# Adafruit_MatrixPortal_S3.net
KiCad netlist of a schematic drawn in EAGLE
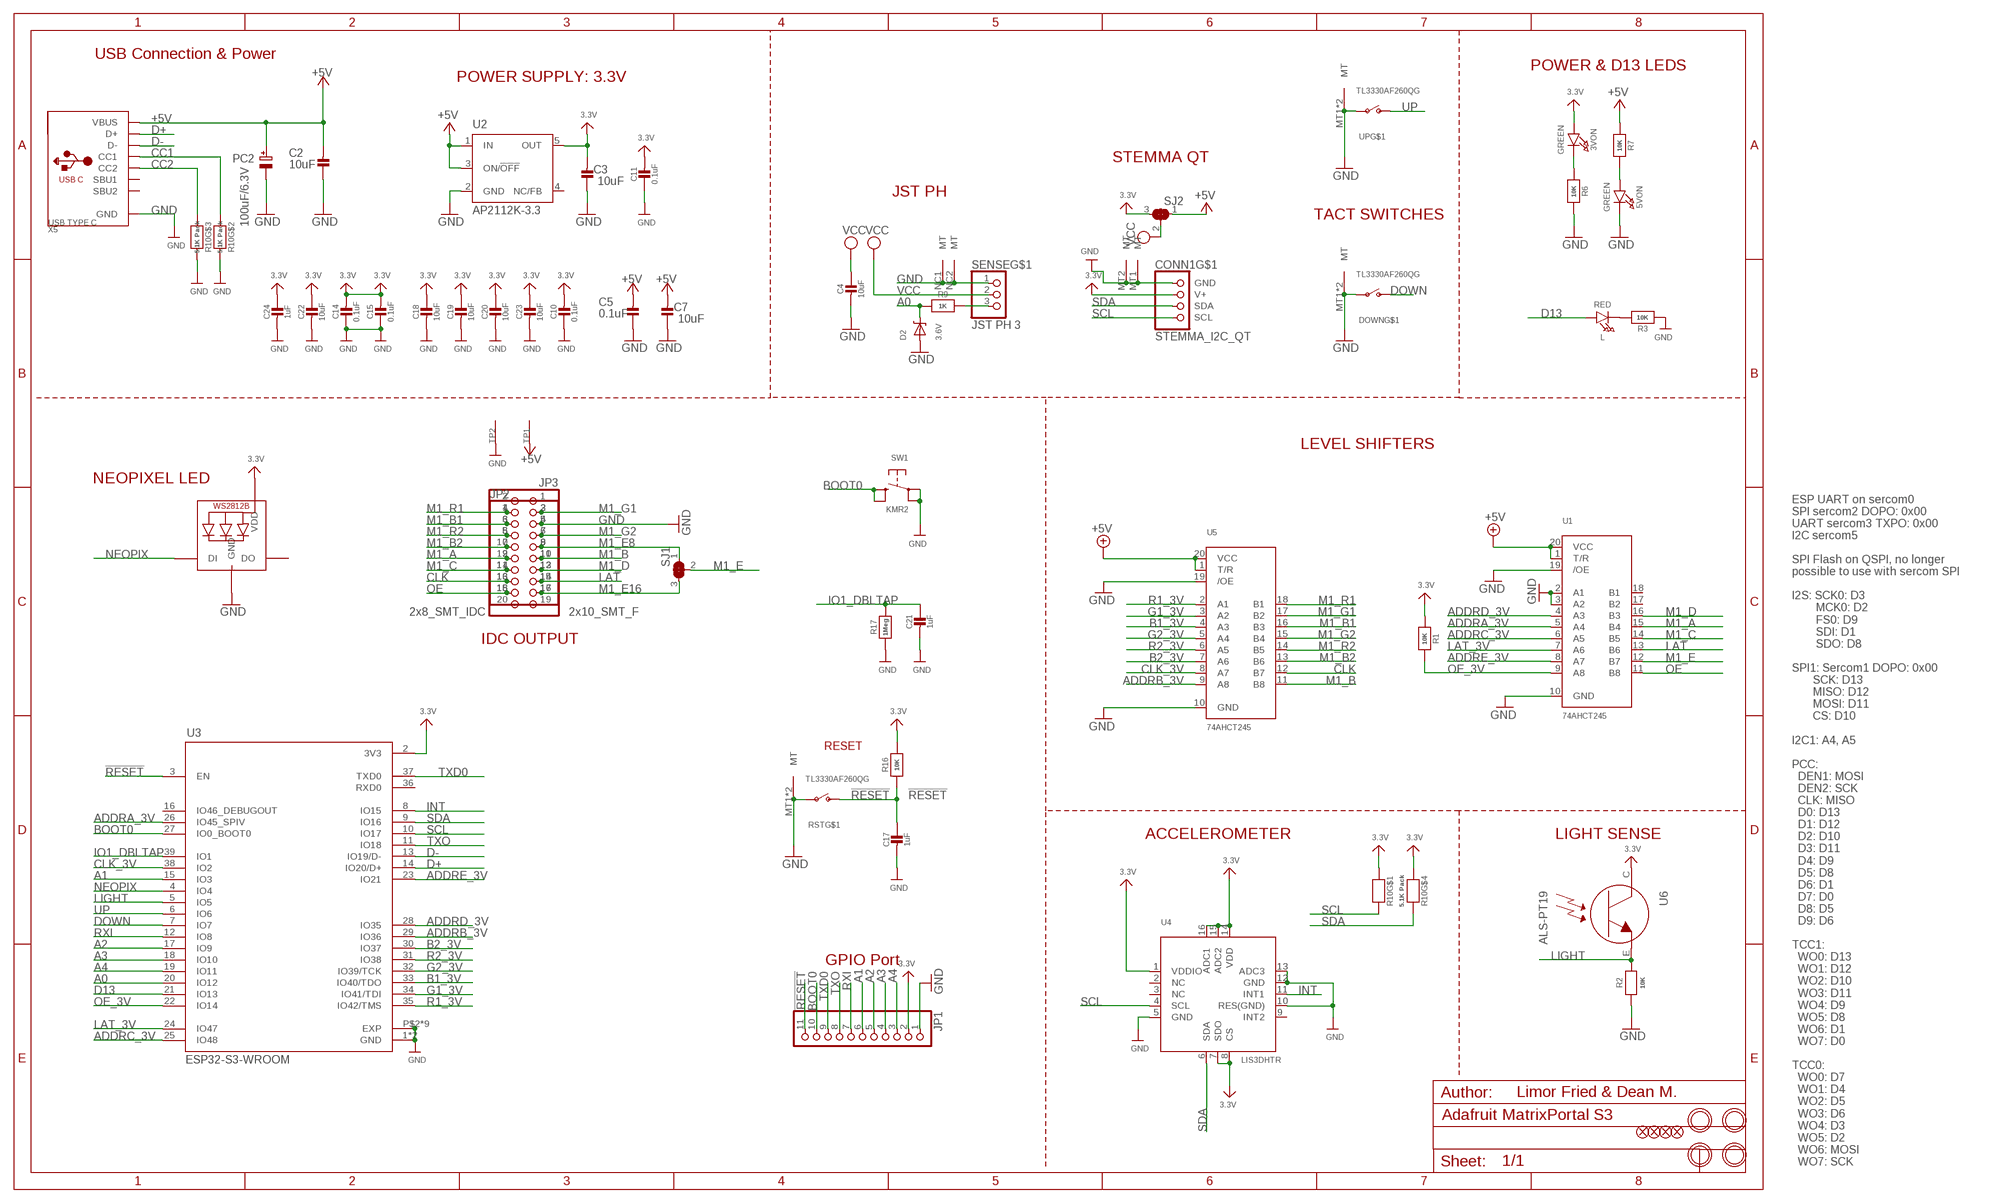
[diagram p0: schematic, sheet 1]

(export (version "E")
  (design (tool "Eeschema 10.0.6"))
  (components
    (comp (ref "3VON")
      (value "GREEN")
      (footprint "eagle-import:CHIPLED_0603_NOOUTLINE")
      (libsource (lib "eagle-import") (part "LED0603_NOOUTLINE"))
    )
    (comp (ref "5VON")
      (value "GREEN")
      (footprint "eagle-import:CHIPLED_0603_NOOUTLINE")
      (libsource (lib "eagle-import") (part "LED0603_NOOUTLINE"))
    )
    (comp (ref "C2")
      (value "10uF")
      (footprint "eagle-import:0805-NO")
      (libsource (lib "eagle-import") (part "CAP_CERAMIC0805-NOOUTLINE"))
    )
    (comp (ref "C3")
      (value "10uF")
      (footprint "eagle-import:0805-NO")
      (libsource (lib "eagle-import") (part "CAP_CERAMIC0805-NOOUTLINE"))
    )
    (comp (ref "C4")
      (value "10uF")
      (footprint "eagle-import:0805-NO")
      (libsource (lib "eagle-import") (part "CAP_CERAMIC0805-NOOUTLINE"))
    )
    (comp (ref "C5")
      (value "0.1uF")
      (footprint "eagle-import:0603-NO")
      (libsource (lib "eagle-import") (part "CAP_CERAMIC0603_NO"))
    )
    (comp (ref "C7")
      (value "10uF")
      (footprint "eagle-import:0805-NO")
      (libsource (lib "eagle-import") (part "CAP_CERAMIC0805-NOOUTLINE"))
    )
    (comp (ref "C10")
      (value "0.1uF")
      (footprint "eagle-import:0603-NO")
      (libsource (lib "eagle-import") (part "CAP_CERAMIC0603_NO"))
    )
    (comp (ref "C11")
      (value "0.1uF")
      (footprint "eagle-import:0603-NO")
      (libsource (lib "eagle-import") (part "CAP_CERAMIC0603_NO"))
    )
    (comp (ref "C14")
      (value "0.1uF")
      (footprint "eagle-import:0603-NO")
      (libsource (lib "eagle-import") (part "CAP_CERAMIC0603_NO"))
    )
    (comp (ref "C15")
      (value "0.1uF")
      (footprint "eagle-import:0603-NO")
      (libsource (lib "eagle-import") (part "CAP_CERAMIC0603_NO"))
    )
    (comp (ref "C17")
      (value "1uF")
      (footprint "eagle-import:0603-NO")
      (libsource (lib "eagle-import") (part "CAP_CERAMIC0603_NO"))
    )
    (comp (ref "C18")
      (value "10uF")
      (footprint "eagle-import:0805-NO")
      (libsource (lib "eagle-import") (part "CAP_CERAMIC0805-NOOUTLINE"))
    )
    (comp (ref "C19")
      (value "10uF")
      (footprint "eagle-import:0805-NO")
      (libsource (lib "eagle-import") (part "CAP_CERAMIC0805-NOOUTLINE"))
    )
    (comp (ref "C20")
      (value "10uF")
      (footprint "eagle-import:0805-NO")
      (libsource (lib "eagle-import") (part "CAP_CERAMIC0805-NOOUTLINE"))
    )
    (comp (ref "C21")
      (value "1uF")
      (footprint "eagle-import:0603-NO")
      (libsource (lib "eagle-import") (part "CAP_CERAMIC0603_NO"))
    )
    (comp (ref "C22")
      (value "10uF")
      (footprint "eagle-import:0805-NO")
      (libsource (lib "eagle-import") (part "CAP_CERAMIC0805-NOOUTLINE"))
    )
    (comp (ref "C23")
      (value "10uF")
      (footprint "eagle-import:0805-NO")
      (libsource (lib "eagle-import") (part "CAP_CERAMIC0805-NOOUTLINE"))
    )
    (comp (ref "C24")
      (value "1uF")
      (footprint "eagle-import:0603-NO")
      (libsource (lib "eagle-import") (part "CAP_CERAMIC0603_NO"))
    )
    (comp (ref "CONN1")
      (value "STEMMA_I2C_QT")
      (footprint "eagle-import:JST_SH4")
      (libsource (lib "eagle-import") (part "STEMMA_I2C_QT"))
    )
    (comp (ref "D2")
      (value "3.6V")
      (footprint "eagle-import:SOD-323")
      (libsource (lib "eagle-import") (part "DIODE-ZENERSOD323"))
    )
    (comp (ref "DOWN")
      (value "TL3330AF260QG")
      (footprint "eagle-import:SPST_TACTILE_RA")
      (libsource (lib "eagle-import") (part "SWITCH_SPST_MNT_TACT_RA"))
    )
    (comp (ref "FID1")
      (value "FIDUCIAL_1MM")
      (footprint "eagle-import:FIDUCIAL_1MM")
      (libsource (lib "eagle-import") (part "FIDUCIAL_1MM"))
    )
    (comp (ref "FID2")
      (value "FIDUCIAL_1MM")
      (footprint "eagle-import:FIDUCIAL_1MM")
      (libsource (lib "eagle-import") (part "FIDUCIAL_1MM"))
    )
    (comp (ref "FID3")
      (value "FIDUCIAL_1MM")
      (footprint "eagle-import:FIDUCIAL_1MM")
      (libsource (lib "eagle-import") (part "FIDUCIAL_1MM"))
    )
    (comp (ref "FID4")
      (value "FIDUCIAL_1MM")
      (footprint "eagle-import:FIDUCIAL_1MM")
      (libsource (lib "eagle-import") (part "FIDUCIAL_1MM"))
    )
    (comp (ref "JP1")
      (value "HEADER-1X11")
      (footprint "eagle-import:1X11_ROUND")
      (libsource (lib "eagle-import") (part "HEADER-1X11"))
    )
    (comp (ref "JP2")
      (value "2x8_SMT_IDC")
      (footprint "eagle-import:2X08_SHROUDEDSMT")
      (libsource (lib "eagle-import") (part "HEADER-2X8_SHROUDEDSMT"))
    )
    (comp (ref "JP3")
      (value "2x10_SMT_F")
      (footprint "eagle-import:2X10_SMT_FEMALE")
      (libsource (lib "eagle-import") (part "HEADER-2X10SMT_FEMALE"))
    )
    (comp (ref "L")
      (value "RED")
      (footprint "eagle-import:CHIPLED_0603_NOOUTLINE")
      (libsource (lib "eagle-import") (part "LED0603_NOOUTLINE"))
    )
    (comp (ref "LED1")
      (value "WS2812B_3535FULL")
      (footprint "eagle-import:LED3535_FULLPADS")
      (libsource (lib "eagle-import") (part "WS2812B_3535FULL"))
    )
    (comp (ref "PC2")
      (value "100uF/6.3V")
      (footprint "eagle-import:PANASONIC_D")
      (libsource (lib "eagle-import") (part "CAP_ELECTROLYTICPANASONIC_D"))
    )
    (comp (ref "R1")
      (value "10K")
      (footprint "eagle-import:0603-NO")
      (libsource (lib "eagle-import") (part "RESISTOR_0603_NOOUT"))
    )
    (comp (ref "R2")
      (value "10K")
      (footprint "eagle-import:0603-NO")
      (libsource (lib "eagle-import") (part "RESISTOR_0603_NOOUT"))
    )
    (comp (ref "R3")
      (value "10K")
      (footprint "eagle-import:0603-NO")
      (libsource (lib "eagle-import") (part "RESISTOR_0603_NOOUT"))
    )
    (comp (ref "R6")
      (value "10K")
      (footprint "eagle-import:0603-NO")
      (libsource (lib "eagle-import") (part "RESISTOR_0603_NOOUT"))
    )
    (comp (ref "R7")
      (value "10K")
      (footprint "eagle-import:0603-NO")
      (libsource (lib "eagle-import") (part "RESISTOR_0603_NOOUT"))
    )
    (comp (ref "R9")
      (value "1K")
      (footprint "eagle-import:0603-NO")
      (libsource (lib "eagle-import") (part "RESISTOR_0603_NOOUT"))
    )
    (comp (ref "R10")
      (value "5.1K Pack")
      (footprint "eagle-import:RESPACK_4X0603")
      (libsource (lib "eagle-import") (part "RESISTOR_4PACK"))
    )
    (comp (ref "R16")
      (value "10K")
      (footprint "eagle-import:0603-NO")
      (libsource (lib "eagle-import") (part "RESISTOR_0603_NOOUT"))
    )
    (comp (ref "R17")
      (value "1Meg")
      (footprint "eagle-import:0603-NO")
      (libsource (lib "eagle-import") (part "RESISTOR_0603_NOOUT"))
    )
    (comp (ref "RST")
      (value "TL3330AF260QG")
      (footprint "eagle-import:SPST_TACTILE_RA")
      (libsource (lib "eagle-import") (part "SWITCH_SPST_MNT_TACT_RA"))
    )
    (comp (ref "SENSE")
      (value "JST PH 3")
      (footprint "eagle-import:JSTPH3")
      (libsource (lib "eagle-import") (part "CON_JST_PH_3PIN"))
    )
    (comp (ref "SJ1")
      (value "SOLDERJUMPER_2WAY")
      (footprint "eagle-import:SOLDERJUMPER_2WAY_OPEN_NOPASTE")
      (libsource (lib "eagle-import") (part "SOLDERJUMPER_2WAY"))
    )
    (comp (ref "SJ2")
      (value "SOLDERJUMPER_2WAY")
      (footprint "eagle-import:SOLDERJUMPER_2WAY_OPEN_NOPASTE")
      (libsource (lib "eagle-import") (part "SOLDERJUMPER_2WAY"))
    )
    (comp (ref "SW1")
      (value "KMR2")
      (footprint "eagle-import:BTN_RKB2_4.6X2.8")
      (libsource (lib "eagle-import") (part "SWITCH_TACT_SMT_RKB2"))
    )
    (comp (ref "TP1")
      (value "SEWTAP_SMTNUTM3")
      (footprint "eagle-import:SMT_NUT_3MM")
      (libsource (lib "eagle-import") (part "SEWTAP_SMTNUTM3"))
    )
    (comp (ref "TP2")
      (value "SEWTAP_SMTNUTM3")
      (footprint "eagle-import:SMT_NUT_3MM")
      (libsource (lib "eagle-import") (part "SEWTAP_SMTNUTM3"))
    )
    (comp (ref "U$14")
      (value "MOUNTINGHOLE2.5")
      (footprint "eagle-import:MOUNTINGHOLE_2.5_PLATED")
      (libsource (lib "eagle-import") (part "MOUNTINGHOLE2.5"))
    )
    (comp (ref "U$19")
      (value "MOUNTINGHOLE2.5")
      (footprint "eagle-import:MOUNTINGHOLE_2.5_PLATED")
      (libsource (lib "eagle-import") (part "MOUNTINGHOLE2.5"))
    )
    (comp (ref "U$22")
      (value "MOUNTINGHOLE2.5")
      (footprint "eagle-import:MOUNTINGHOLE_2.5_PLATED")
      (libsource (lib "eagle-import") (part "MOUNTINGHOLE2.5"))
    )
    (comp (ref "U$24")
      (value "MOUNTINGHOLE2.5")
      (footprint "eagle-import:MOUNTINGHOLE_2.5_PLATED")
      (libsource (lib "eagle-import") (part "MOUNTINGHOLE2.5"))
    )
    (comp (ref "U1")
      (value "74AHCT245")
      (footprint "eagle-import:TSSOP20")
      (libsource (lib "eagle-import") (part "74LCX245_TSSOP20"))
    )
    (comp (ref "U2")
      (value "AP2112K-3.3")
      (footprint "eagle-import:SOT23-DBV")
      (libsource (lib "eagle-import") (part "LP2985-XXDBVR33"))
    )
    (comp (ref "U3")
      (value "ESP32-S3-WROOM")
      (footprint "eagle-import:S3-WROOM32")
      (libsource (lib "eagle-import") (part "ESP32-S3-WROOM"))
    )
    (comp (ref "U4")
      (value "LIS3DHTR")
      (footprint "eagle-import:LGA16_3X3MM")
      (libsource (lib "eagle-import") (part "ACCEL_LIS3DHTR"))
    )
    (comp (ref "U5")
      (value "74AHCT245")
      (footprint "eagle-import:TSSOP20")
      (libsource (lib "eagle-import") (part "74LCX245_TSSOP20"))
    )
    (comp (ref "U6")
      (value "ALS-PT19")
      (footprint "eagle-import:ALS-PT19-315C")
      (libsource (lib "eagle-import") (part "PHOTOTRANSISTOR_PT19-315C"))
    )
    (comp (ref "UP")
      (value "TL3330AF260QG")
      (footprint "eagle-import:SPST_TACTILE_RA")
      (libsource (lib "eagle-import") (part "SWITCH_SPST_MNT_TACT_RA"))
    )
    (comp (ref "X5")
      (value "USB TYPE C")
      (footprint "eagle-import:USB_C_CUSB31-CFM2AX-01-X")
      (libsource (lib "eagle-import") (part "USB_C"))
    )
  )
  (nets
    (net (code "1") (name "+5V") (class "Default")
      (node (ref "C2") (pin "2") (pinfunction "2_2") (pintype "passive"))
      (node (ref "C5") (pin "2") (pinfunction "2_2") (pintype "passive"))
      (node (ref "C7") (pin "2") (pinfunction "2_2") (pintype "passive"))
      (node (ref "PC2") (pin "+") (pinfunction "+_+") (pintype "passive"))
      (node (ref "R7") (pin "1") (pinfunction "1_1") (pintype "passive"))
      (node (ref "SJ2") (pin "1") (pinfunction "1_1") (pintype "passive"))
      (node (ref "TP1") (pin "P$1") (pinfunction "SEW_P$1") (pintype "bidirectional"))
      (node (ref "U1") (pin "1") (pinfunction "T/R_1") (pintype "bidirectional"))
      (node (ref "U1") (pin "20") (pinfunction "VCC_20") (pintype "bidirectional"))
      (node (ref "U2") (pin "1") (pinfunction "IN_1") (pintype "input"))
      (node (ref "U2") (pin "3") (pinfunction "ON/~{OFF}_3") (pintype "input"))
      (node (ref "U5") (pin "1") (pinfunction "T/R_1") (pintype "bidirectional"))
      (node (ref "U5") (pin "20") (pinfunction "VCC_20") (pintype "bidirectional"))
      (node (ref "X5") (pin "A4B9") (pinfunction "VBUS_A4B9") (pintype "power_in"))
      (node (ref "X5") (pin "B4A9") (pinfunction "VBUS_B4A9") (pintype "power_in"))
    )
    (net (code "2") (name "/A0") (class "Default")
      (node (ref "D2") (pin "C") (pinfunction "C_C") (pintype "passive"))
      (node (ref "R9") (pin "2") (pinfunction "2_2") (pintype "passive"))
      (node (ref "U3") (pin "20") (pinfunction "IO12_20") (pintype "bidirectional"))
    )
    (net (code "3") (name "/A1") (class "Default")
      (node (ref "JP1") (pin "6") (pinfunction "6_6") (pintype "passive"))
      (node (ref "U3") (pin "15") (pinfunction "IO3_15") (pintype "bidirectional"))
    )
    (net (code "4") (name "/A2") (class "Default")
      (node (ref "JP1") (pin "5") (pinfunction "5_5") (pintype "passive"))
      (node (ref "U3") (pin "17") (pinfunction "IO9_17") (pintype "bidirectional"))
    )
    (net (code "5") (name "/A3") (class "Default")
      (node (ref "JP1") (pin "4") (pinfunction "4_4") (pintype "passive"))
      (node (ref "U3") (pin "18") (pinfunction "IO10_18") (pintype "bidirectional"))
    )
    (net (code "6") (name "/A4") (class "Default")
      (node (ref "JP1") (pin "3") (pinfunction "3_3") (pintype "passive"))
      (node (ref "U3") (pin "19") (pinfunction "IO11_19") (pintype "bidirectional"))
    )
    (net (code "7") (name "/ADDRA_3V") (class "Default")
      (node (ref "U1") (pin "5") (pinfunction "A4_5") (pintype "bidirectional"))
      (node (ref "U3") (pin "26") (pinfunction "IO45_SPIV_26") (pintype "bidirectional"))
    )
    (net (code "8") (name "/ADDRB_3V") (class "Default")
      (node (ref "U3") (pin "29") (pinfunction "IO36_29") (pintype "bidirectional"))
      (node (ref "U5") (pin "9") (pinfunction "A8_9") (pintype "bidirectional"))
    )
    (net (code "9") (name "/ADDRC_3V") (class "Default")
      (node (ref "U1") (pin "6") (pinfunction "A5_6") (pintype "bidirectional"))
      (node (ref "U3") (pin "25") (pinfunction "IO48_25") (pintype "input"))
    )
    (net (code "10") (name "/ADDRD_3V") (class "Default")
      (node (ref "U1") (pin "4") (pinfunction "A3_4") (pintype "bidirectional"))
      (node (ref "U3") (pin "28") (pinfunction "IO35_28") (pintype "input"))
    )
    (net (code "11") (name "/ADDRE_3V") (class "Default")
      (node (ref "U1") (pin "8") (pinfunction "A7_8") (pintype "bidirectional"))
      (node (ref "U3") (pin "23") (pinfunction "IO21_23") (pintype "bidirectional"))
    )
    (net (code "12") (name "/B1_3V") (class "Default")
      (node (ref "U3") (pin "33") (pinfunction "IO40/TDO_33") (pintype "bidirectional"))
      (node (ref "U5") (pin "4") (pinfunction "A3_4") (pintype "bidirectional"))
    )
    (net (code "13") (name "/B2_3V") (class "Default")
      (node (ref "U3") (pin "30") (pinfunction "IO37_30") (pintype "bidirectional"))
      (node (ref "U5") (pin "7") (pinfunction "A6_7") (pintype "bidirectional"))
    )
    (net (code "14") (name "/BOOT0") (class "Default")
      (node (ref "JP1") (pin "10") (pinfunction "10_10") (pintype "passive"))
      (node (ref "SW1") (pin "B") (pinfunction "S_B") (pintype "passive"))
      (node (ref "SW1") (pin "B'") (pinfunction "S1_B'") (pintype "passive"))
      (node (ref "U3") (pin "27") (pinfunction "IO0_BOOT0_27") (pintype "bidirectional"))
    )
    (net (code "15") (name "/CC1") (class "Default")
      (node (ref "R10") (pin "2") (pinfunction "1_2") (pintype "passive"))
      (node (ref "X5") (pin "A5") (pinfunction "CC1_A5") (pintype "bidirectional"))
    )
    (net (code "16") (name "/CC2") (class "Default")
      (node (ref "R10") (pin "3") (pinfunction "1_3") (pintype "passive"))
      (node (ref "X5") (pin "B5") (pinfunction "CC2_B5") (pintype "bidirectional"))
    )
    (net (code "17") (name "/CLK") (class "Default")
      (node (ref "JP2") (pin "13") (pinfunction "13_13") (pintype "passive"))
      (node (ref "JP3") (pin "16") (pinfunction "16_16") (pintype "passive"))
      (node (ref "U5") (pin "12") (pinfunction "B7_12") (pintype "bidirectional"))
    )
    (net (code "18") (name "/CLK_3V") (class "Default")
      (node (ref "U3") (pin "38") (pinfunction "IO2_38") (pintype "bidirectional"))
      (node (ref "U5") (pin "8") (pinfunction "A7_8") (pintype "bidirectional"))
    )
    (net (code "19") (name "/D+") (class "Default")
      (node (ref "U3") (pin "14") (pinfunction "IO20/D+_14") (pintype "bidirectional"))
      (node (ref "X5") (pin "A6") (pinfunction "D+_A6") (pintype "bidirectional"))
      (node (ref "X5") (pin "B6") (pinfunction "D+_B6") (pintype "bidirectional"))
    )
    (net (code "20") (name "/D-") (class "Default")
      (node (ref "U3") (pin "13") (pinfunction "IO19/D-_13") (pintype "bidirectional"))
      (node (ref "X5") (pin "A7") (pinfunction "D-_A7") (pintype "bidirectional"))
      (node (ref "X5") (pin "B7") (pinfunction "D-_B7") (pintype "bidirectional"))
    )
    (net (code "21") (name "/D13") (class "Default")
      (node (ref "L") (pin "A") (pinfunction "A_A") (pintype "passive"))
      (node (ref "U3") (pin "21") (pinfunction "IO13_21") (pintype "bidirectional"))
    )
    (net (code "22") (name "/DOWN") (class "Default")
      (node (ref "DOWN") (pin "2") (pinfunction "S_2") (pintype "passive"))
      (node (ref "U3") (pin "7") (pinfunction "IO7_7") (pintype "bidirectional"))
    )
    (net (code "23") (name "/G1_3V") (class "Default")
      (node (ref "U3") (pin "34") (pinfunction "IO41/TDI_34") (pintype "bidirectional"))
      (node (ref "U5") (pin "3") (pinfunction "A2_3") (pintype "bidirectional"))
    )
    (net (code "24") (name "/G2_3V") (class "Default")
      (node (ref "U3") (pin "32") (pinfunction "IO39/TCK_32") (pintype "bidirectional"))
      (node (ref "U5") (pin "5") (pinfunction "A4_5") (pintype "bidirectional"))
    )
    (net (code "25") (name "/INT") (class "Default")
      (node (ref "U3") (pin "8") (pinfunction "IO15_8") (pintype "bidirectional"))
      (node (ref "U4") (pin "11") (pinfunction "INT1_11") (pintype "output"))
    )
    (net (code "26") (name "/IO1_DBLTAP") (class "Default")
      (node (ref "C21") (pin "1") (pinfunction "1_1") (pintype "passive"))
      (node (ref "R17") (pin "2") (pinfunction "2_2") (pintype "passive"))
      (node (ref "U3") (pin "39") (pinfunction "IO1_39") (pintype "bidirectional"))
    )
    (net (code "27") (name "/LAT") (class "Default")
      (node (ref "JP2") (pin "14") (pinfunction "14_14") (pintype "passive"))
      (node (ref "JP3") (pin "15") (pinfunction "15_15") (pintype "passive"))
      (node (ref "U1") (pin "13") (pinfunction "B6_13") (pintype "bidirectional"))
    )
    (net (code "28") (name "/LAT_3V") (class "Default")
      (node (ref "U1") (pin "7") (pinfunction "A6_7") (pintype "bidirectional"))
      (node (ref "U3") (pin "24") (pinfunction "IO47_24") (pintype "bidirectional"))
    )
    (net (code "29") (name "/LIGHT") (class "Default")
      (node (ref "R2") (pin "1") (pinfunction "1_1") (pintype "passive"))
      (node (ref "U3") (pin "5") (pinfunction "IO5_5") (pintype "bidirectional"))
      (node (ref "U6") (pin "E") (pinfunction "E_E") (pintype "bidirectional"))
    )
    (net (code "30") (name "/M1_A") (class "Default")
      (node (ref "JP2") (pin "9") (pinfunction "9_9") (pintype "passive"))
      (node (ref "JP3") (pin "12") (pinfunction "12_12") (pintype "passive"))
      (node (ref "U1") (pin "15") (pinfunction "B4_15") (pintype "bidirectional"))
    )
    (net (code "31") (name "/M1_B") (class "Default")
      (node (ref "JP2") (pin "10") (pinfunction "10_10") (pintype "passive"))
      (node (ref "JP3") (pin "11") (pinfunction "11_11") (pintype "passive"))
      (node (ref "U5") (pin "11") (pinfunction "B8_11") (pintype "bidirectional"))
    )
    (net (code "32") (name "/M1_B1") (class "Default")
      (node (ref "JP2") (pin "3") (pinfunction "3_3") (pintype "passive"))
      (node (ref "JP3") (pin "6") (pinfunction "6_6") (pintype "passive"))
      (node (ref "U5") (pin "16") (pinfunction "B3_16") (pintype "bidirectional"))
    )
    (net (code "33") (name "/M1_B2") (class "Default")
      (node (ref "JP2") (pin "7") (pinfunction "7_7") (pintype "passive"))
      (node (ref "JP3") (pin "10") (pinfunction "10_10") (pintype "passive"))
      (node (ref "U5") (pin "13") (pinfunction "B6_13") (pintype "bidirectional"))
    )
    (net (code "34") (name "/M1_C") (class "Default")
      (node (ref "JP2") (pin "11") (pinfunction "11_11") (pintype "passive"))
      (node (ref "JP3") (pin "14") (pinfunction "14_14") (pintype "passive"))
      (node (ref "U1") (pin "14") (pinfunction "B5_14") (pintype "bidirectional"))
    )
    (net (code "35") (name "/M1_D") (class "Default")
      (node (ref "JP2") (pin "12") (pinfunction "12_12") (pintype "passive"))
      (node (ref "JP3") (pin "13") (pinfunction "13_13") (pintype "passive"))
      (node (ref "U1") (pin "16") (pinfunction "B3_16") (pintype "bidirectional"))
    )
    (net (code "36") (name "/M1_E") (class "Default")
      (node (ref "SJ1") (pin "2") (pinfunction "2_2") (pintype "passive"))
      (node (ref "U1") (pin "12") (pinfunction "B7_12") (pintype "bidirectional"))
    )
    (net (code "37") (name "/M1_E8") (class "Default")
      (node (ref "JP2") (pin "8") (pinfunction "8_8") (pintype "passive"))
      (node (ref "JP3") (pin "9") (pinfunction "9_9") (pintype "passive"))
      (node (ref "SJ1") (pin "1") (pinfunction "1_1") (pintype "passive"))
    )
    (net (code "38") (name "/M1_E16") (class "Default")
      (node (ref "JP2") (pin "16") (pinfunction "16_16") (pintype "passive"))
      (node (ref "JP3") (pin "17") (pinfunction "17_17") (pintype "passive"))
      (node (ref "SJ1") (pin "3") (pinfunction "3_3") (pintype "passive"))
    )
    (net (code "39") (name "/M1_G1") (class "Default")
      (node (ref "JP2") (pin "2") (pinfunction "2_2") (pintype "passive"))
      (node (ref "JP3") (pin "3") (pinfunction "3_3") (pintype "passive"))
      (node (ref "U5") (pin "17") (pinfunction "B2_17") (pintype "bidirectional"))
    )
    (net (code "40") (name "/M1_G2") (class "Default")
      (node (ref "JP2") (pin "6") (pinfunction "6_6") (pintype "passive"))
      (node (ref "JP3") (pin "7") (pinfunction "7_7") (pintype "passive"))
      (node (ref "U5") (pin "15") (pinfunction "B4_15") (pintype "bidirectional"))
    )
    (net (code "41") (name "/M1_R1") (class "Default")
      (node (ref "JP2") (pin "1") (pinfunction "1_1") (pintype "passive"))
      (node (ref "JP3") (pin "4") (pinfunction "4_4") (pintype "passive"))
      (node (ref "U5") (pin "18") (pinfunction "B1_18") (pintype "bidirectional"))
    )
    (net (code "42") (name "/M1_R2") (class "Default")
      (node (ref "JP2") (pin "5") (pinfunction "5_5") (pintype "passive"))
      (node (ref "JP3") (pin "8") (pinfunction "8_8") (pintype "passive"))
      (node (ref "U5") (pin "14") (pinfunction "B5_14") (pintype "bidirectional"))
    )
    (net (code "43") (name "/NEOPIX") (class "Default")
      (node (ref "LED1") (pin "1") (pinfunction "DI_1") (pintype "input"))
      (node (ref "U3") (pin "4") (pinfunction "IO4_4") (pintype "bidirectional"))
    )
    (net (code "44") (name "/OE") (class "Default")
      (node (ref "JP2") (pin "15") (pinfunction "15_15") (pintype "passive"))
      (node (ref "JP3") (pin "18") (pinfunction "18_18") (pintype "passive"))
      (node (ref "U1") (pin "11") (pinfunction "B8_11") (pintype "bidirectional"))
    )
    (net (code "45") (name "/OE_3V") (class "Default")
      (node (ref "R1") (pin "2") (pinfunction "2_2") (pintype "passive"))
      (node (ref "U1") (pin "9") (pinfunction "A8_9") (pintype "bidirectional"))
      (node (ref "U3") (pin "22") (pinfunction "IO14_22") (pintype "bidirectional"))
    )
    (net (code "46") (name "/R1_3V") (class "Default")
      (node (ref "U3") (pin "35") (pinfunction "IO42/TMS_35") (pintype "bidirectional"))
      (node (ref "U5") (pin "2") (pinfunction "A1_2") (pintype "bidirectional"))
    )
    (net (code "47") (name "/R2_3V") (class "Default")
      (node (ref "U3") (pin "31") (pinfunction "IO38_31") (pintype "bidirectional"))
      (node (ref "U5") (pin "6") (pinfunction "A5_6") (pintype "bidirectional"))
    )
    (net (code "48") (name "/RXI") (class "Default")
      (node (ref "JP1") (pin "7") (pinfunction "7_7") (pintype "passive"))
      (node (ref "U3") (pin "12") (pinfunction "IO8_12") (pintype "bidirectional"))
    )
    (net (code "49") (name "/SCL") (class "Default")
      (node (ref "CONN1") (pin "4") (pinfunction "SCL_4") (pintype "passive"))
      (node (ref "R10") (pin "8") (pinfunction "2_8") (pintype "passive"))
      (node (ref "U3") (pin "10") (pinfunction "IO17_10") (pintype "bidirectional"))
      (node (ref "U4") (pin "4") (pinfunction "SCL_4") (pintype "bidirectional"))
    )
    (net (code "50") (name "/SDA") (class "Default")
      (node (ref "CONN1") (pin "3") (pinfunction "SDA_3") (pintype "passive"))
      (node (ref "R10") (pin "5") (pinfunction "2_5") (pintype "passive"))
      (node (ref "U3") (pin "9") (pinfunction "IO16_9") (pintype "bidirectional"))
      (node (ref "U4") (pin "6") (pinfunction "SDA_6") (pintype "bidirectional"))
    )
    (net (code "51") (name "/TXD0") (class "Default")
      (node (ref "JP1") (pin "9") (pinfunction "9_9") (pintype "passive"))
      (node (ref "U3") (pin "37") (pinfunction "TXD0_37") (pintype "bidirectional"))
    )
    (net (code "52") (name "/TXO") (class "Default")
      (node (ref "JP1") (pin "8") (pinfunction "8_8") (pintype "passive"))
      (node (ref "U3") (pin "11") (pinfunction "IO18_11") (pintype "bidirectional"))
    )
    (net (code "53") (name "/UP") (class "Default")
      (node (ref "U3") (pin "6") (pinfunction "IO6_6") (pintype "bidirectional"))
      (node (ref "UP") (pin "2") (pinfunction "S_2") (pintype "passive"))
    )
    (net (code "54") (name "/~{RESET}") (class "Default")
      (node (ref "C17") (pin "1") (pinfunction "1_1") (pintype "passive"))
      (node (ref "JP1") (pin "11") (pinfunction "11_11") (pintype "passive"))
      (node (ref "R16") (pin "1") (pinfunction "1_1") (pintype "passive"))
      (node (ref "RST") (pin "2") (pinfunction "S_2") (pintype "passive"))
      (node (ref "U3") (pin "3") (pinfunction "EN_3") (pintype "input"))
    )
    (net (code "55") (name "3.3V") (class "Default")
      (node (ref "3VON") (pin "A") (pinfunction "A_A") (pintype "passive"))
      (node (ref "C10") (pin "2") (pinfunction "2_2") (pintype "passive"))
      (node (ref "C11") (pin "2") (pinfunction "2_2") (pintype "passive"))
      (node (ref "C14") (pin "2") (pinfunction "2_2") (pintype "passive"))
      (node (ref "C15") (pin "2") (pinfunction "2_2") (pintype "passive"))
      (node (ref "C18") (pin "1") (pinfunction "1_1") (pintype "passive"))
      (node (ref "C19") (pin "1") (pinfunction "1_1") (pintype "passive"))
      (node (ref "C20") (pin "1") (pinfunction "1_1") (pintype "passive"))
      (node (ref "C22") (pin "1") (pinfunction "1_1") (pintype "passive"))
      (node (ref "C23") (pin "1") (pinfunction "1_1") (pintype "passive"))
      (node (ref "C24") (pin "1") (pinfunction "1_1") (pintype "passive"))
      (node (ref "C3") (pin "2") (pinfunction "2_2") (pintype "passive"))
      (node (ref "CONN1") (pin "2") (pinfunction "V+_2") (pintype "passive"))
      (node (ref "JP1") (pin "2") (pinfunction "2_2") (pintype "passive"))
      (node (ref "LED1") (pin "2") (pinfunction "VDD_2") (pintype "power_in"))
      (node (ref "R1") (pin "1") (pinfunction "1_1") (pintype "passive"))
      (node (ref "R10") (pin "1") (pinfunction "1_1") (pintype "passive"))
      (node (ref "R10") (pin "4") (pinfunction "1_4") (pintype "passive"))
      (node (ref "R16") (pin "2") (pinfunction "2_2") (pintype "passive"))
      (node (ref "SJ2") (pin "3") (pinfunction "3_3") (pintype "passive"))
      (node (ref "U2") (pin "5") (pinfunction "OUT_5") (pintype "passive"))
      (node (ref "U3") (pin "2") (pinfunction "3V3_2") (pintype "power_in"))
      (node (ref "U4") (pin "1") (pinfunction "VDDIO_1") (pintype "power_in"))
      (node (ref "U4") (pin "14") (pinfunction "VDD_14") (pintype "power_in"))
      (node (ref "U4") (pin "15") (pinfunction "ADC2_15") (pintype "input"))
      (node (ref "U4") (pin "16") (pinfunction "ADC1_16") (pintype "input"))
      (node (ref "U4") (pin "7") (pinfunction "SDO_7") (pintype "bidirectional"))
      (node (ref "U4") (pin "8") (pinfunction "CS_8") (pintype "input"))
      (node (ref "U6") (pin "C") (pinfunction "C_C") (pintype "bidirectional"))
    )
    (net (code "56") (name "GND") (class "Default")
      (node (ref "5VON") (pin "C") (pinfunction "C_C") (pintype "passive"))
      (node (ref "C10") (pin "1") (pinfunction "1_1") (pintype "passive"))
      (node (ref "C11") (pin "1") (pinfunction "1_1") (pintype "passive"))
      (node (ref "C14") (pin "1") (pinfunction "1_1") (pintype "passive"))
      (node (ref "C15") (pin "1") (pinfunction "1_1") (pintype "passive"))
      (node (ref "C17") (pin "2") (pinfunction "2_2") (pintype "passive"))
      (node (ref "C18") (pin "2") (pinfunction "2_2") (pintype "passive"))
      (node (ref "C19") (pin "2") (pinfunction "2_2") (pintype "passive"))
      (node (ref "C2") (pin "1") (pinfunction "1_1") (pintype "passive"))
      (node (ref "C20") (pin "2") (pinfunction "2_2") (pintype "passive"))
      (node (ref "C21") (pin "2") (pinfunction "2_2") (pintype "passive"))
      (node (ref "C22") (pin "2") (pinfunction "2_2") (pintype "passive"))
      (node (ref "C23") (pin "2") (pinfunction "2_2") (pintype "passive"))
      (node (ref "C24") (pin "2") (pinfunction "2_2") (pintype "passive"))
      (node (ref "C3") (pin "1") (pinfunction "1_1") (pintype "passive"))
      (node (ref "C4") (pin "2") (pinfunction "2_2") (pintype "passive"))
      (node (ref "C5") (pin "1") (pinfunction "1_1") (pintype "passive"))
      (node (ref "C7") (pin "1") (pinfunction "1_1") (pintype "passive"))
      (node (ref "CONN1") (pin "1") (pinfunction "GND_1") (pintype "passive"))
      (node (ref "CONN1") (pin "MT1") (pinfunction "MT_MT1") (pintype "bidirectional"))
      (node (ref "CONN1") (pin "MT2") (pinfunction "MT_MT2") (pintype "bidirectional"))
      (node (ref "D2") (pin "A") (pinfunction "A_A") (pintype "passive"))
      (node (ref "DOWN") (pin "1") (pinfunction "P_1") (pintype "passive"))
      (node (ref "DOWN") (pin "MT1") (pinfunction "MT_MT1") (pintype "bidirectional"))
      (node (ref "DOWN") (pin "MT2") (pinfunction "MT_MT2") (pintype "bidirectional"))
      (node (ref "JP1") (pin "1") (pinfunction "1_1") (pintype "passive"))
      (node (ref "JP2") (pin "4") (pinfunction "4_4") (pintype "passive"))
      (node (ref "JP3") (pin "5") (pinfunction "5_5") (pintype "passive"))
      (node (ref "LED1") (pin "4") (pinfunction "GND_4") (pintype "power_in"))
      (node (ref "PC2") (pin "-") (pinfunction "-_-") (pintype "passive"))
      (node (ref "R10") (pin "6") (pinfunction "2_6") (pintype "passive"))
      (node (ref "R10") (pin "7") (pinfunction "2_7") (pintype "passive"))
      (node (ref "R17") (pin "1") (pinfunction "1_1") (pintype "passive"))
      (node (ref "R2") (pin "2") (pinfunction "2_2") (pintype "passive"))
      (node (ref "R3") (pin "2") (pinfunction "2_2") (pintype "passive"))
      (node (ref "R6") (pin "2") (pinfunction "2_2") (pintype "passive"))
      (node (ref "RST") (pin "1") (pinfunction "P_1") (pintype "passive"))
      (node (ref "RST") (pin "MT1") (pinfunction "MT_MT1") (pintype "bidirectional"))
      (node (ref "RST") (pin "MT2") (pinfunction "MT_MT2") (pintype "bidirectional"))
      (node (ref "SENSE") (pin "1") (pinfunction "1_1") (pintype "passive"))
      (node (ref "SENSE") (pin "NC1") (pinfunction "MT_NC1") (pintype "bidirectional"))
      (node (ref "SENSE") (pin "NC2") (pinfunction "MT_NC2") (pintype "bidirectional"))
      (node (ref "SW1") (pin "A") (pinfunction "P_A") (pintype "passive"))
      (node (ref "SW1") (pin "A'") (pinfunction "P1_A'") (pintype "passive"))
      (node (ref "TP2") (pin "P$1") (pinfunction "SEW_P$1") (pintype "bidirectional"))
      (node (ref "U1") (pin "10") (pinfunction "GND_10") (pintype "bidirectional"))
      (node (ref "U1") (pin "19") (pinfunction "/OE_19") (pintype "bidirectional"))
      (node (ref "U1") (pin "2") (pinfunction "A1_2") (pintype "bidirectional"))
      (node (ref "U1") (pin "3") (pinfunction "A2_3") (pintype "bidirectional"))
      (node (ref "U2") (pin "2") (pinfunction "GND_2") (pintype "power_in"))
      (node (ref "U3") (pin "1") (pinfunction "GND_1") (pintype "power_in"))
      (node (ref "U3") (pin "40") (pinfunction "GND_40") (pintype "power_in"))
      (node (ref "U3") (pin "P$10") (pinfunction "EXP_P$10") (pintype "power_in"))
      (node (ref "U3") (pin "P$2") (pinfunction "EXP_P$2") (pintype "power_in"))
      (node (ref "U3") (pin "P$3") (pinfunction "EXP_P$3") (pintype "power_in"))
      (node (ref "U3") (pin "P$4") (pinfunction "EXP_P$4") (pintype "power_in"))
      (node (ref "U3") (pin "P$5") (pinfunction "EXP_P$5") (pintype "power_in"))
      (node (ref "U3") (pin "P$6") (pinfunction "EXP_P$6") (pintype "power_in"))
      (node (ref "U3") (pin "P$7") (pinfunction "EXP_P$7") (pintype "power_in"))
      (node (ref "U3") (pin "P$8") (pinfunction "EXP_P$8") (pintype "power_in"))
      (node (ref "U3") (pin "P$9") (pinfunction "EXP_P$9") (pintype "power_in"))
      (node (ref "U4") (pin "10") (pinfunction "RES(GND)_10") (pintype "bidirectional"))
      (node (ref "U4") (pin "12") (pinfunction "GND_12") (pintype "power_in"))
      (node (ref "U4") (pin "13") (pinfunction "ADC3_13") (pintype "input"))
      (node (ref "U4") (pin "5") (pinfunction "GND_5") (pintype "power_in"))
      (node (ref "U5") (pin "10") (pinfunction "GND_10") (pintype "bidirectional"))
      (node (ref "U5") (pin "19") (pinfunction "/OE_19") (pintype "bidirectional"))
      (node (ref "UP") (pin "1") (pinfunction "P_1") (pintype "passive"))
      (node (ref "UP") (pin "MT1") (pinfunction "MT_MT1") (pintype "bidirectional"))
      (node (ref "UP") (pin "MT2") (pinfunction "MT_MT2") (pintype "bidirectional"))
      (node (ref "X5") (pin "A1B12") (pinfunction "GND_A1B12") (pintype "power_in"))
      (node (ref "X5") (pin "B1A12") (pinfunction "GND_B1A12") (pintype "power_in"))
    )
    (net (code "57") (name "Net-(3VON-PadC)") (class "Default")
      (node (ref "3VON") (pin "C") (pinfunction "C_C") (pintype "passive"))
      (node (ref "R6") (pin "1") (pinfunction "1_1") (pintype "passive"))
    )
    (net (code "58") (name "Net-(5VON-PadA)") (class "Default")
      (node (ref "5VON") (pin "A") (pinfunction "A_A") (pintype "passive"))
      (node (ref "R7") (pin "2") (pinfunction "2_2") (pintype "passive"))
    )
    (net (code "59") (name "Net-(L-PadC)") (class "Default")
      (node (ref "L") (pin "C") (pinfunction "C_C") (pintype "passive"))
      (node (ref "R3") (pin "1") (pinfunction "1_1") (pintype "passive"))
    )
    (net (code "60") (name "Net-(R9-Pad1)") (class "Default")
      (node (ref "R9") (pin "1") (pinfunction "1_1") (pintype "passive"))
      (node (ref "SENSE") (pin "3") (pinfunction "3_3") (pintype "passive"))
    )
    (net (code "61") (name "VCC") (class "Default")
      (node (ref "C4") (pin "1") (pinfunction "1_1") (pintype "passive"))
      (node (ref "SENSE") (pin "2") (pinfunction "2_2") (pintype "passive"))
      (node (ref "SJ2") (pin "2") (pinfunction "2_2") (pintype "passive"))
    )
    (net (code "62") (name "unconnected-(JP3-Pad1)") (class "Default")
      (node (ref "JP3") (pin "1") (pinfunction "1_1") (pintype "passive"))
    )
    (net (code "63") (name "unconnected-(JP3-Pad2)") (class "Default")
      (node (ref "JP3") (pin "2") (pinfunction "2_2") (pintype "passive"))
    )
    (net (code "64") (name "unconnected-(JP3-Pad19)") (class "Default")
      (node (ref "JP3") (pin "19") (pinfunction "19_19") (pintype "passive"))
    )
    (net (code "65") (name "unconnected-(JP3-Pad20)") (class "Default")
      (node (ref "JP3") (pin "20") (pinfunction "20_20") (pintype "passive"))
    )
    (net (code "66") (name "unconnected-(LED1-DO-Pad3)") (class "Default")
      (node (ref "LED1") (pin "3") (pinfunction "DO_3") (pintype "output"))
    )
    (net (code "67") (name "unconnected-(U1-B1-Pad18)") (class "Default")
      (node (ref "U1") (pin "18") (pinfunction "B1_18") (pintype "bidirectional"))
    )
    (net (code "68") (name "unconnected-(U1-B2-Pad17)") (class "Default")
      (node (ref "U1") (pin "17") (pinfunction "B2_17") (pintype "bidirectional"))
    )
    (net (code "69") (name "unconnected-(U2-NC{slash}FB-Pad4)") (class "Default")
      (node (ref "U2") (pin "4") (pinfunction "NC/FB_4") (pintype "passive"))
    )
    (net (code "70") (name "unconnected-(U3-IO46_DEBUGOUT-Pad16)") (class "Default")
      (node (ref "U3") (pin "16") (pinfunction "IO46_DEBUGOUT_16") (pintype "input"))
    )
    (net (code "71") (name "unconnected-(U3-RXD0-Pad36)") (class "Default")
      (node (ref "U3") (pin "36") (pinfunction "RXD0_36") (pintype "bidirectional"))
    )
    (net (code "72") (name "unconnected-(U4-INT2-Pad9)") (class "Default")
      (node (ref "U4") (pin "9") (pinfunction "INT2_9") (pintype "output"))
    )
    (net (code "73") (name "unconnected-(U4-NC-Pad2)") (class "Default")
      (node (ref "U4") (pin "2") (pinfunction "NC_2") (pintype "no_connect"))
    )
    (net (code "74") (name "unconnected-(U4-NC-Pad3)") (class "Default")
      (node (ref "U4") (pin "3") (pinfunction "NC_3") (pintype "no_connect"))
    )
    (net (code "75") (name "unconnected-(X5-SBU1-PadA8)") (class "Default")
      (node (ref "X5") (pin "A8") (pinfunction "SBU1_A8") (pintype "bidirectional"))
    )
    (net (code "76") (name "unconnected-(X5-SBU2-PadB8)") (class "Default")
      (node (ref "X5") (pin "B8") (pinfunction "SBU2_B8") (pintype "bidirectional"))
    )
  )
)
